# ReboostV2__Isense.net
KiCad netlist of a schematic drawn in Altium Designer
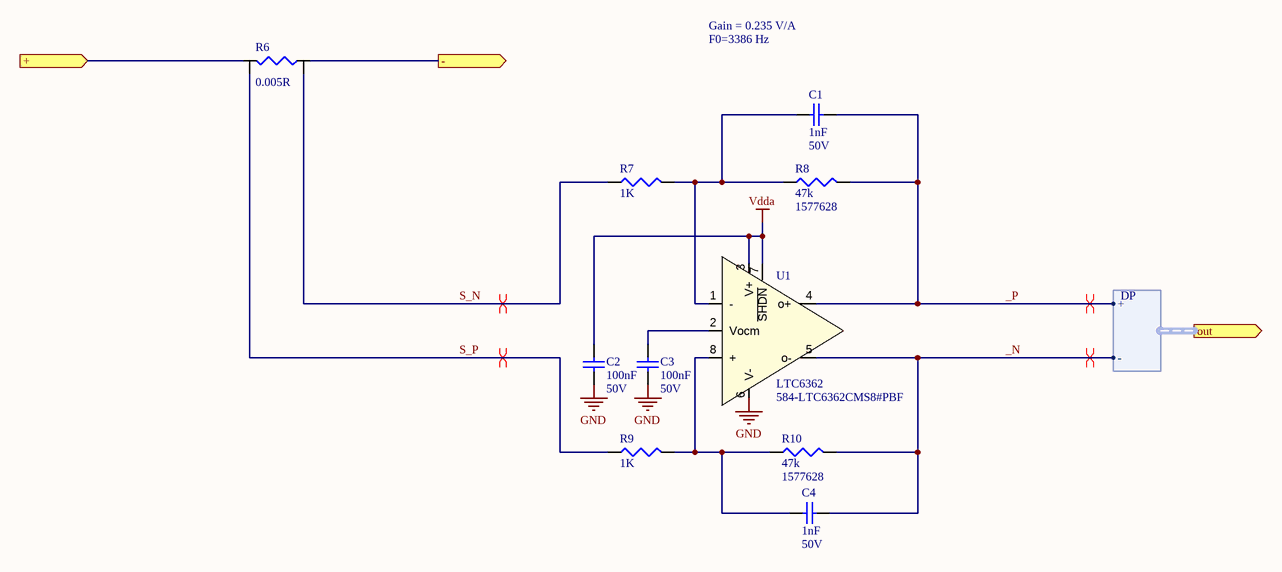
[diagram p0: ReboostV2__Isense.SchDoc]

(export (version "E")
  (design (tool "Eeschema 10.0.6"))
  (components
    (comp (ref "C1")
      (value "1nF")
      (footprint "C0603")
      (description "Capacitor, 1nF, 50V, X7R")
      (fields (field (name "VOLTAGE RATING") "50V"))
      (libsource (lib "AR_Capacitors_Ceramic") (part "1nF/0603/CER/50V"))
    )
    (comp (ref "C2")
      (value "100nF")
      (footprint "C0603")
      (description "Capacitor, 100nF, 50V, X7R")
      (fields (field (name "VOLTAGE RATING") "50V"))
      (libsource (lib "AR_Capacitors_Ceramic") (part "100nF/0603/CER/50V"))
    )
    (comp (ref "C3")
      (value "100nF")
      (footprint "C0603")
      (description "Capacitor, 100nF, 50V, X7R")
      (fields (field (name "VOLTAGE RATING") "50V"))
      (libsource (lib "AR_Capacitors_Ceramic") (part "100nF/0603/CER/50V"))
    )
    (comp (ref "C4")
      (value "1nF")
      (footprint "C0603")
      (description "Capacitor, 1nF, 50V, X7R")
      (fields (field (name "VOLTAGE RATING") "50V"))
      (libsource (lib "AR_Capacitors_Ceramic") (part "1nF/0603/CER/50V"))
    )
    (comp (ref "R6")
      (value "0.005R")
      (footprint "2512-L-4T")
      (description "Resistor, 0.005R, 1%, 2W, 50PPM")
      (libsource (lib "AR_Resistors_SMD") (part "0.005/2512/2000W/200V"))
    )
    (comp (ref "R7")
      (value "1K")
      (footprint "0603")
      (description "Resistor, 1K, 1%, 0.063W, 50V, 100PPM, 0603")
      (libsource (lib "AR_Resistors_SMD") (part "1K/0603/0063W/50V"))
    )
    (comp (ref "R8")
      (value "47k")
      (footprint "0603")
      (description "Resistor, 47K, 0.1%, 0.063W, 50V, 100PPM, 0603")
      (fields (field (name "SUPPLIER PART NUMBER 1") "1577628"))
      (libsource (lib "AR_Resistors_SMD") (part "47K/0603/0063W/50V_1"))
    )
    (comp (ref "R9")
      (value "1K")
      (footprint "0603")
      (description "Resistor, 1K, 1%, 0.063W, 50V, 100PPM, 0603")
      (libsource (lib "AR_Resistors_SMD") (part "1K/0603/0063W/50V"))
    )
    (comp (ref "R10")
      (value "47k")
      (footprint "0603")
      (description "Resistor, 47K, 0.1%, 0.063W, 50V, 100PPM, 0603")
      (fields (field (name "SUPPLIER PART NUMBER 1") "1577628"))
      (libsource (lib "AR_Resistors_SMD") (part "47K/0603/0063W/50V_1"))
    )
    (comp (ref "U1")
      (value "LTC6362")
      (footprint "MSOP8")
      (description "Precision, Low Power Rail-to-Rail Input/Output Differential Op Amp")
      (fields (field (name "SUPPLIER PART NUMBER 1") "584-LTC6362CMS8#PBF"))
      (libsource (lib "AR_ICs") (part "LTC6362HMS8"))
    )
  )
  (nets
    (net (code "2") (name "/+") (class "Default")
      (node (ref "R6") (pin "1") (pinfunction "1_1") (pintype "passive"))
    )
    (net (code "3") (name "/-") (class "Default")
      (node (ref "R6") (pin "2") (pinfunction "2_2") (pintype "passive"))
    )
    (net (code "4") (name "/S_N") (class "Default")
      (node (ref "R6") (pin "4") (pinfunction "4_4") (pintype "passive"))
      (node (ref "R7") (pin "1") (pinfunction "1_1") (pintype "passive"))
    )
    (net (code "5") (name "/S_P") (class "Default")
      (node (ref "R6") (pin "3") (pinfunction "3_3") (pintype "passive"))
      (node (ref "R9") (pin "1") (pinfunction "1_1") (pintype "passive"))
    )
    (net (code "6") (name "/_N") (class "Default")
      (node (ref "C4") (pin "2") (pinfunction "2_2") (pintype "passive"))
      (node (ref "R10") (pin "2") (pinfunction "2_2") (pintype "passive"))
      (node (ref "U1") (pin "5") (pinfunction "o-_5") (pintype "passive"))
    )
    (net (code "7") (name "/_P") (class "Default")
      (node (ref "C1") (pin "2") (pinfunction "2_2") (pintype "passive"))
      (node (ref "R8") (pin "2") (pinfunction "2_2") (pintype "passive"))
      (node (ref "U1") (pin "4") (pinfunction "o+_4") (pintype "passive"))
    )
    (net (code "9") (name "GND") (class "Default")
      (node (ref "C2") (pin "1") (pinfunction "1_1") (pintype "passive"))
      (node (ref "C3") (pin "1") (pinfunction "1_1") (pintype "passive"))
      (node (ref "U1") (pin "6") (pinfunction "V-_6") (pintype "passive"))
    )
    (net (code "10") (name "Net-(U1-+)") (class "Default")
      (node (ref "C4") (pin "1") (pinfunction "1_1") (pintype "passive"))
      (node (ref "R10") (pin "1") (pinfunction "1_1") (pintype "passive"))
      (node (ref "R9") (pin "2") (pinfunction "2_2") (pintype "passive"))
      (node (ref "U1") (pin "8") (pinfunction "+_8") (pintype "passive"))
    )
    (net (code "11") (name "Net-(U1--)") (class "Default")
      (node (ref "C1") (pin "1") (pinfunction "1_1") (pintype "passive"))
      (node (ref "R7") (pin "2") (pinfunction "2_2") (pintype "passive"))
      (node (ref "R8") (pin "1") (pinfunction "1_1") (pintype "passive"))
      (node (ref "U1") (pin "1") (pinfunction "-_1") (pintype "passive"))
    )
    (net (code "12") (name "Net-(U1-Vocm)") (class "Default")
      (node (ref "C3") (pin "2") (pinfunction "2_2") (pintype "passive"))
      (node (ref "U1") (pin "2") (pinfunction "Vocm_2") (pintype "passive"))
    )
    (net (code "13") (name "Vdda") (class "Default")
      (node (ref "C2") (pin "2") (pinfunction "2_2") (pintype "passive"))
      (node (ref "U1") (pin "3") (pinfunction "V+_3") (pintype "passive"))
      (node (ref "U1") (pin "7") (pinfunction "~{SHDN}_7") (pintype "passive"))
    )
  )
)
